# CKT_se_al_senoidal_como_entrada_analogic.net
KiCad netlist of a schematic drawn in EAGLE
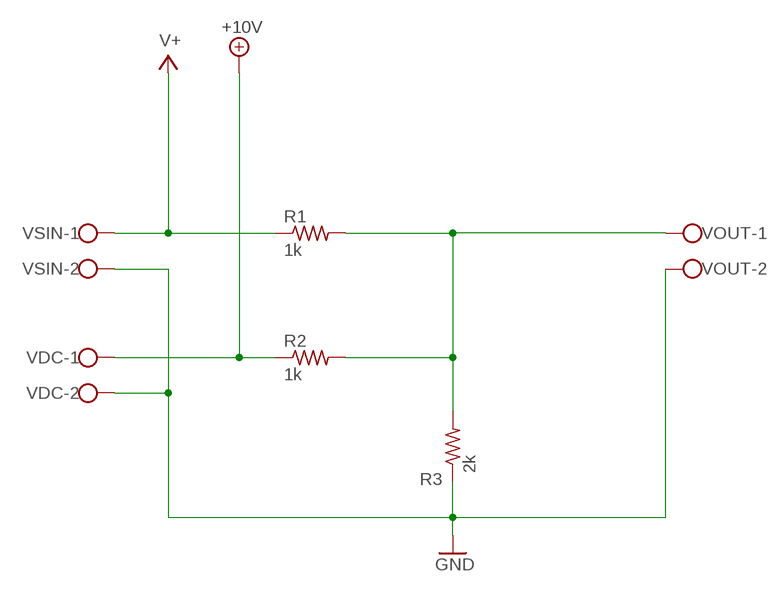
[diagram p0: schematic, sheet 1]

(export (version "E")
  (design (tool "Eeschema 10.0.6"))
  (components
    (comp (ref "R1")
      (value "1k")
      (footprint "eagle-import:0207_10")
      (libsource (lib "eagle-import") (part "R-US_0207/10"))
    )
    (comp (ref "R2")
      (value "1k")
      (footprint "eagle-import:0207_10")
      (libsource (lib "eagle-import") (part "R-US_0207/10"))
    )
    (comp (ref "R3")
      (value "2k")
      (footprint "eagle-import:0207_10")
      (libsource (lib "eagle-import") (part "R-US_0207/10"))
    )
    (comp (ref "VDC")
      (value "W237-102")
      (footprint "eagle-import:W237-102")
      (fields (field (name "MPN") "237-102"))
      (libsource (lib "eagle-import") (part "W237-102"))
    )
    (comp (ref "VOUT")
      (value "W237-102")
      (footprint "eagle-import:W237-102")
      (fields (field (name "MPN") "237-102"))
      (libsource (lib "eagle-import") (part "W237-102"))
    )
    (comp (ref "VSIN")
      (value "W237-102")
      (footprint "eagle-import:W237-102")
      (fields (field (name "MPN") "237-102"))
      (libsource (lib "eagle-import") (part "W237-102"))
    )
  )
  (nets
    (net (code "1") (name "+10V") (class "Default")
      (node (ref "R2") (pin "1") (pinfunction "1_1") (pintype "passive"))
      (node (ref "VDC") (pin "1") (pinfunction "KL_1") (pintype "passive"))
    )
    (net (code "2") (name "GND") (class "Default")
      (node (ref "R3") (pin "1") (pinfunction "1_1") (pintype "passive"))
      (node (ref "VDC") (pin "2") (pinfunction "KL_2") (pintype "passive"))
      (node (ref "VOUT") (pin "2") (pinfunction "KL_2") (pintype "passive"))
      (node (ref "VSIN") (pin "2") (pinfunction "KL_2") (pintype "passive"))
    )
    (net (code "3") (name "Net-(VOUTA-KL)") (class "Default")
      (node (ref "R1") (pin "2") (pinfunction "2_2") (pintype "passive"))
      (node (ref "R2") (pin "2") (pinfunction "2_2") (pintype "passive"))
      (node (ref "R3") (pin "2") (pinfunction "2_2") (pintype "passive"))
      (node (ref "VOUT") (pin "1") (pinfunction "KL_1") (pintype "passive"))
    )
    (net (code "4") (name "V+") (class "Default")
      (node (ref "R1") (pin "1") (pinfunction "1_1") (pintype "passive"))
      (node (ref "VSIN") (pin "1") (pinfunction "KL_1") (pintype "passive"))
    )
  )
)
